# sensor_board_ma700.net
KiCad netlist of a schematic drawn in EAGLE
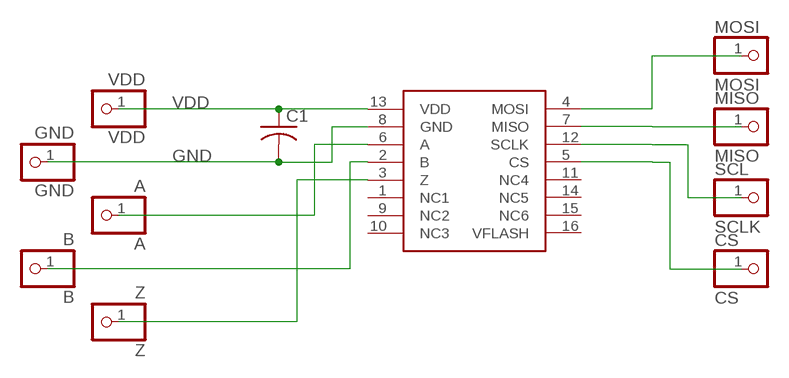
[diagram p0: schematic, sheet 1]

(export (version "E")
  (design (tool "Eeschema 10.0.6"))
  (components
    (comp (ref "A")
      (value "A")
      (footprint "eagle-import:1X01")
      (libsource (lib "eagle-import") (part "PINHD-1X1"))
    )
    (comp (ref "B")
      (value "B")
      (footprint "eagle-import:1X01")
      (libsource (lib "eagle-import") (part "PINHD-1X1"))
    )
    (comp (ref "C1")
      (value "C-USC0603")
      (footprint "eagle-import:C0603")
      (libsource (lib "eagle-import") (part "C-USC0603"))
    )
    (comp (ref "CS")
      (value "CS")
      (footprint "eagle-import:1X01")
      (libsource (lib "eagle-import") (part "PINHD-1X1"))
    )
    (comp (ref "GND")
      (value "GND")
      (footprint "eagle-import:1X01")
      (libsource (lib "eagle-import") (part "PINHD-1X1"))
    )
    (comp (ref "MA700")
      (value "MA700")
      (footprint "eagle-import:QFN16")
      (libsource (lib "eagle-import") (part "MA700"))
    )
    (comp (ref "MISO")
      (value "MISO")
      (footprint "eagle-import:1X01")
      (libsource (lib "eagle-import") (part "PINHD-1X1"))
    )
    (comp (ref "MOSI")
      (value "MOSI")
      (footprint "eagle-import:1X01")
      (libsource (lib "eagle-import") (part "PINHD-1X1"))
    )
    (comp (ref "SCL")
      (value "SCLK")
      (footprint "eagle-import:1X01")
      (libsource (lib "eagle-import") (part "PINHD-1X1"))
    )
    (comp (ref "VDD")
      (value "VDD")
      (footprint "eagle-import:1X01")
      (libsource (lib "eagle-import") (part "PINHD-1X1"))
    )
    (comp (ref "Z")
      (value "Z")
      (footprint "eagle-import:1X01")
      (libsource (lib "eagle-import") (part "PINHD-1X1"))
    )
  )
  (nets
    (net (code "1") (name "/GND") (class "Default")
      (node (ref "C1") (pin "2") (pinfunction "2_2") (pintype "passive"))
      (node (ref "GND") (pin "1") (pinfunction "1_1") (pintype "passive"))
      (node (ref "MA700") (pin "8") (pinfunction "GND_8") (pintype "bidirectional"))
    )
    (net (code "2") (name "/VDD") (class "Default")
      (node (ref "C1") (pin "1") (pinfunction "1_1") (pintype "passive"))
      (node (ref "MA700") (pin "13") (pinfunction "VDD_13") (pintype "bidirectional"))
      (node (ref "VDD") (pin "1") (pinfunction "1_1") (pintype "passive"))
    )
    (net (code "3") (name "Net-(MA700-A)") (class "Default")
      (node (ref "A") (pin "1") (pinfunction "1_1") (pintype "passive"))
      (node (ref "MA700") (pin "6") (pinfunction "A_6") (pintype "bidirectional"))
    )
    (net (code "4") (name "Net-(MA700-B)") (class "Default")
      (node (ref "B") (pin "1") (pinfunction "1_1") (pintype "passive"))
      (node (ref "MA700") (pin "2") (pinfunction "B_2") (pintype "bidirectional"))
    )
    (net (code "5") (name "Net-(MA700-CS)") (class "Default")
      (node (ref "CS") (pin "1") (pinfunction "1_1") (pintype "passive"))
      (node (ref "MA700") (pin "5") (pinfunction "CS_5") (pintype "bidirectional"))
    )
    (net (code "6") (name "Net-(MA700-MISO)") (class "Default")
      (node (ref "MA700") (pin "7") (pinfunction "MISO_7") (pintype "bidirectional"))
      (node (ref "MISO") (pin "1") (pinfunction "1_1") (pintype "passive"))
    )
    (net (code "7") (name "Net-(MA700-MOSI)") (class "Default")
      (node (ref "MA700") (pin "4") (pinfunction "MOSI_4") (pintype "bidirectional"))
      (node (ref "MOSI") (pin "1") (pinfunction "1_1") (pintype "passive"))
    )
    (net (code "8") (name "Net-(MA700-SCLK)") (class "Default")
      (node (ref "MA700") (pin "12") (pinfunction "SCLK_12") (pintype "bidirectional"))
      (node (ref "SCL") (pin "1") (pinfunction "1_1") (pintype "passive"))
    )
    (net (code "9") (name "Net-(MA700-Z)") (class "Default")
      (node (ref "MA700") (pin "3") (pinfunction "Z_3") (pintype "bidirectional"))
      (node (ref "Z") (pin "1") (pinfunction "1_1") (pintype "passive"))
    )
    (net (code "10") (name "unconnected-(MA700-NC1-Pad1)") (class "Default")
      (node (ref "MA700") (pin "1") (pinfunction "NC1_1") (pintype "bidirectional"))
    )
    (net (code "11") (name "unconnected-(MA700-NC2-Pad9)") (class "Default")
      (node (ref "MA700") (pin "9") (pinfunction "NC2_9") (pintype "bidirectional"))
    )
    (net (code "12") (name "unconnected-(MA700-NC3-Pad10)") (class "Default")
      (node (ref "MA700") (pin "10") (pinfunction "NC3_10") (pintype "bidirectional"))
    )
    (net (code "13") (name "unconnected-(MA700-NC4-Pad11)") (class "Default")
      (node (ref "MA700") (pin "11") (pinfunction "NC4_11") (pintype "bidirectional"))
    )
    (net (code "14") (name "unconnected-(MA700-NC5-Pad14)") (class "Default")
      (node (ref "MA700") (pin "14") (pinfunction "NC5_14") (pintype "bidirectional"))
    )
    (net (code "15") (name "unconnected-(MA700-NC6-Pad15)") (class "Default")
      (node (ref "MA700") (pin "15") (pinfunction "NC6_15") (pintype "bidirectional"))
    )
    (net (code "16") (name "unconnected-(MA700-VFLASH-Pad16)") (class "Default")
      (node (ref "MA700") (pin "16") (pinfunction "VFLASH_16") (pintype "bidirectional"))
    )
  )
)
